# ParticleTestv2.net
KiCad netlist of a schematic drawn in EAGLE
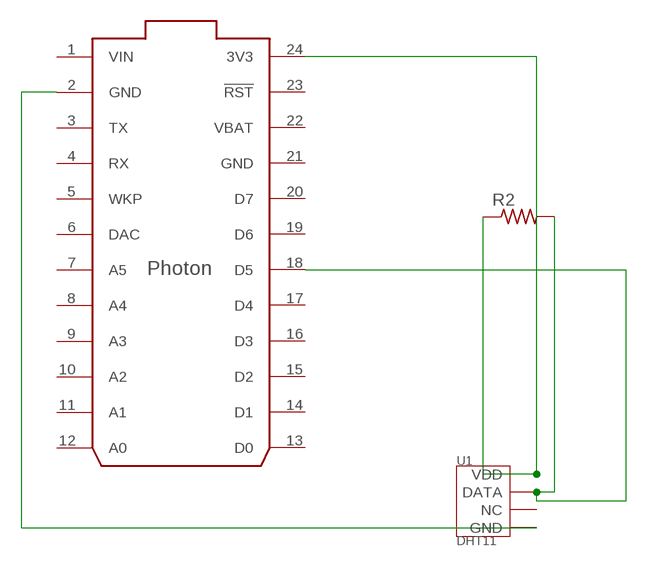
[diagram p0: schematic, sheet 1]

(export (version "E")
  (design (tool "Eeschema 10.0.6"))
  (components
    (comp (ref "R2")
      (value "R-US_R0805")
      (footprint "eagle-import:R0805")
      (libsource (lib "eagle-import") (part "R-US_R0805"))
    )
    (comp (ref "U$1")
      (value "PHOTON_WITH_HEADERS")
      (footprint "eagle-import:PHOTON")
      (libsource (lib "eagle-import") (part "PHOTON_WITH_HEADERS"))
    )
    (comp (ref "U1")
      (value "DHT11")
      (footprint "eagle-import:SNR4-2.54-15.5X12.0X5.5MM")
      (libsource (lib "eagle-import") (part "TEM-HUM-DHT11(4P-15.5X12.0MM)"))
    )
  )
  (nets
    (net (code "1") (name "/GND") (class "Default")
      (node (ref "U$1") (pin "21") (pinfunction "GND_21") (pintype "power_in"))
    )
    (net (code "2") (name "/VBAT") (class "Default")
      (node (ref "U$1") (pin "22") (pinfunction "VBAT_22") (pintype "power_in"))
    )
    (net (code "3") (name "/VIN") (class "Default")
      (node (ref "U$1") (pin "1") (pinfunction "VIN_1") (pintype "power_in"))
    )
    (net (code "4") (name "Net-(U$1-3V3)") (class "Default")
      (node (ref "R2") (pin "1") (pinfunction "1_1") (pintype "passive"))
      (node (ref "U$1") (pin "24") (pinfunction "3V3_24") (pintype "power_in"))
      (node (ref "U1") (pin "1") (pinfunction "VDD_1") (pintype "power_in"))
    )
    (net (code "5") (name "Net-(U$1-D5)") (class "Default")
      (node (ref "R2") (pin "2") (pinfunction "2_2") (pintype "passive"))
      (node (ref "U$1") (pin "18") (pinfunction "D5_18") (pintype "bidirectional"))
      (node (ref "U1") (pin "2") (pinfunction "DATA_2") (pintype "bidirectional"))
    )
    (net (code "6") (name "Net-(U1-GND)") (class "Default")
      (node (ref "U$1") (pin "2") (pinfunction "GND_2") (pintype "power_in"))
      (node (ref "U1") (pin "4") (pinfunction "GND_4") (pintype "power_in"))
    )
    (net (code "7") (name "unconnected-(U$1-A0-Pad12)") (class "Default")
      (node (ref "U$1") (pin "12") (pinfunction "A0_12") (pintype "bidirectional"))
    )
    (net (code "8") (name "unconnected-(U$1-A1-Pad11)") (class "Default")
      (node (ref "U$1") (pin "11") (pinfunction "A1_11") (pintype "bidirectional"))
    )
    (net (code "9") (name "unconnected-(U$1-A2-Pad10)") (class "Default")
      (node (ref "U$1") (pin "10") (pinfunction "A2_10") (pintype "bidirectional"))
    )
    (net (code "10") (name "unconnected-(U$1-A3-Pad9)") (class "Default")
      (node (ref "U$1") (pin "9") (pinfunction "A3_9") (pintype "bidirectional"))
    )
    (net (code "11") (name "unconnected-(U$1-A4-Pad8)") (class "Default")
      (node (ref "U$1") (pin "8") (pinfunction "A4_8") (pintype "bidirectional"))
    )
    (net (code "12") (name "unconnected-(U$1-A5-Pad7)") (class "Default")
      (node (ref "U$1") (pin "7") (pinfunction "A5_7") (pintype "bidirectional"))
    )
    (net (code "13") (name "unconnected-(U$1-D0-Pad13)") (class "Default")
      (node (ref "U$1") (pin "13") (pinfunction "D0_13") (pintype "bidirectional"))
    )
    (net (code "14") (name "unconnected-(U$1-D1-Pad14)") (class "Default")
      (node (ref "U$1") (pin "14") (pinfunction "D1_14") (pintype "bidirectional"))
    )
    (net (code "15") (name "unconnected-(U$1-D2-Pad15)") (class "Default")
      (node (ref "U$1") (pin "15") (pinfunction "D2_15") (pintype "bidirectional"))
    )
    (net (code "16") (name "unconnected-(U$1-D3-Pad16)") (class "Default")
      (node (ref "U$1") (pin "16") (pinfunction "D3_16") (pintype "bidirectional"))
    )
    (net (code "17") (name "unconnected-(U$1-D4-Pad17)") (class "Default")
      (node (ref "U$1") (pin "17") (pinfunction "D4_17") (pintype "bidirectional"))
    )
    (net (code "18") (name "unconnected-(U$1-D6-Pad19)") (class "Default")
      (node (ref "U$1") (pin "19") (pinfunction "D6_19") (pintype "bidirectional"))
    )
    (net (code "19") (name "unconnected-(U$1-D7-Pad20)") (class "Default")
      (node (ref "U$1") (pin "20") (pinfunction "D7_20") (pintype "bidirectional"))
    )
    (net (code "20") (name "unconnected-(U$1-DAC-Pad6)") (class "Default")
      (node (ref "U$1") (pin "6") (pinfunction "DAC_6") (pintype "bidirectional"))
    )
    (net (code "21") (name "unconnected-(U$1-RX-Pad4)") (class "Default")
      (node (ref "U$1") (pin "4") (pinfunction "RX_4") (pintype "bidirectional"))
    )
    (net (code "22") (name "unconnected-(U$1-TX-Pad3)") (class "Default")
      (node (ref "U$1") (pin "3") (pinfunction "TX_3") (pintype "bidirectional"))
    )
    (net (code "23") (name "unconnected-(U$1-WKP-Pad5)") (class "Default")
      (node (ref "U$1") (pin "5") (pinfunction "WKP_5") (pintype "bidirectional"))
    )
    (net (code "24") (name "unconnected-(U$1-~{RST}-Pad23)") (class "Default")
      (node (ref "U$1") (pin "23") (pinfunction "~{RST}_23") (pintype "bidirectional"))
    )
    (net (code "25") (name "unconnected-(U1-NC-Pad3)") (class "Default")
      (node (ref "U1") (pin "3") (pinfunction "NC_3") (pintype "no_connect"))
    )
  )
)
